# ticc.net
KiCad netlist of a schematic drawn in EAGLE
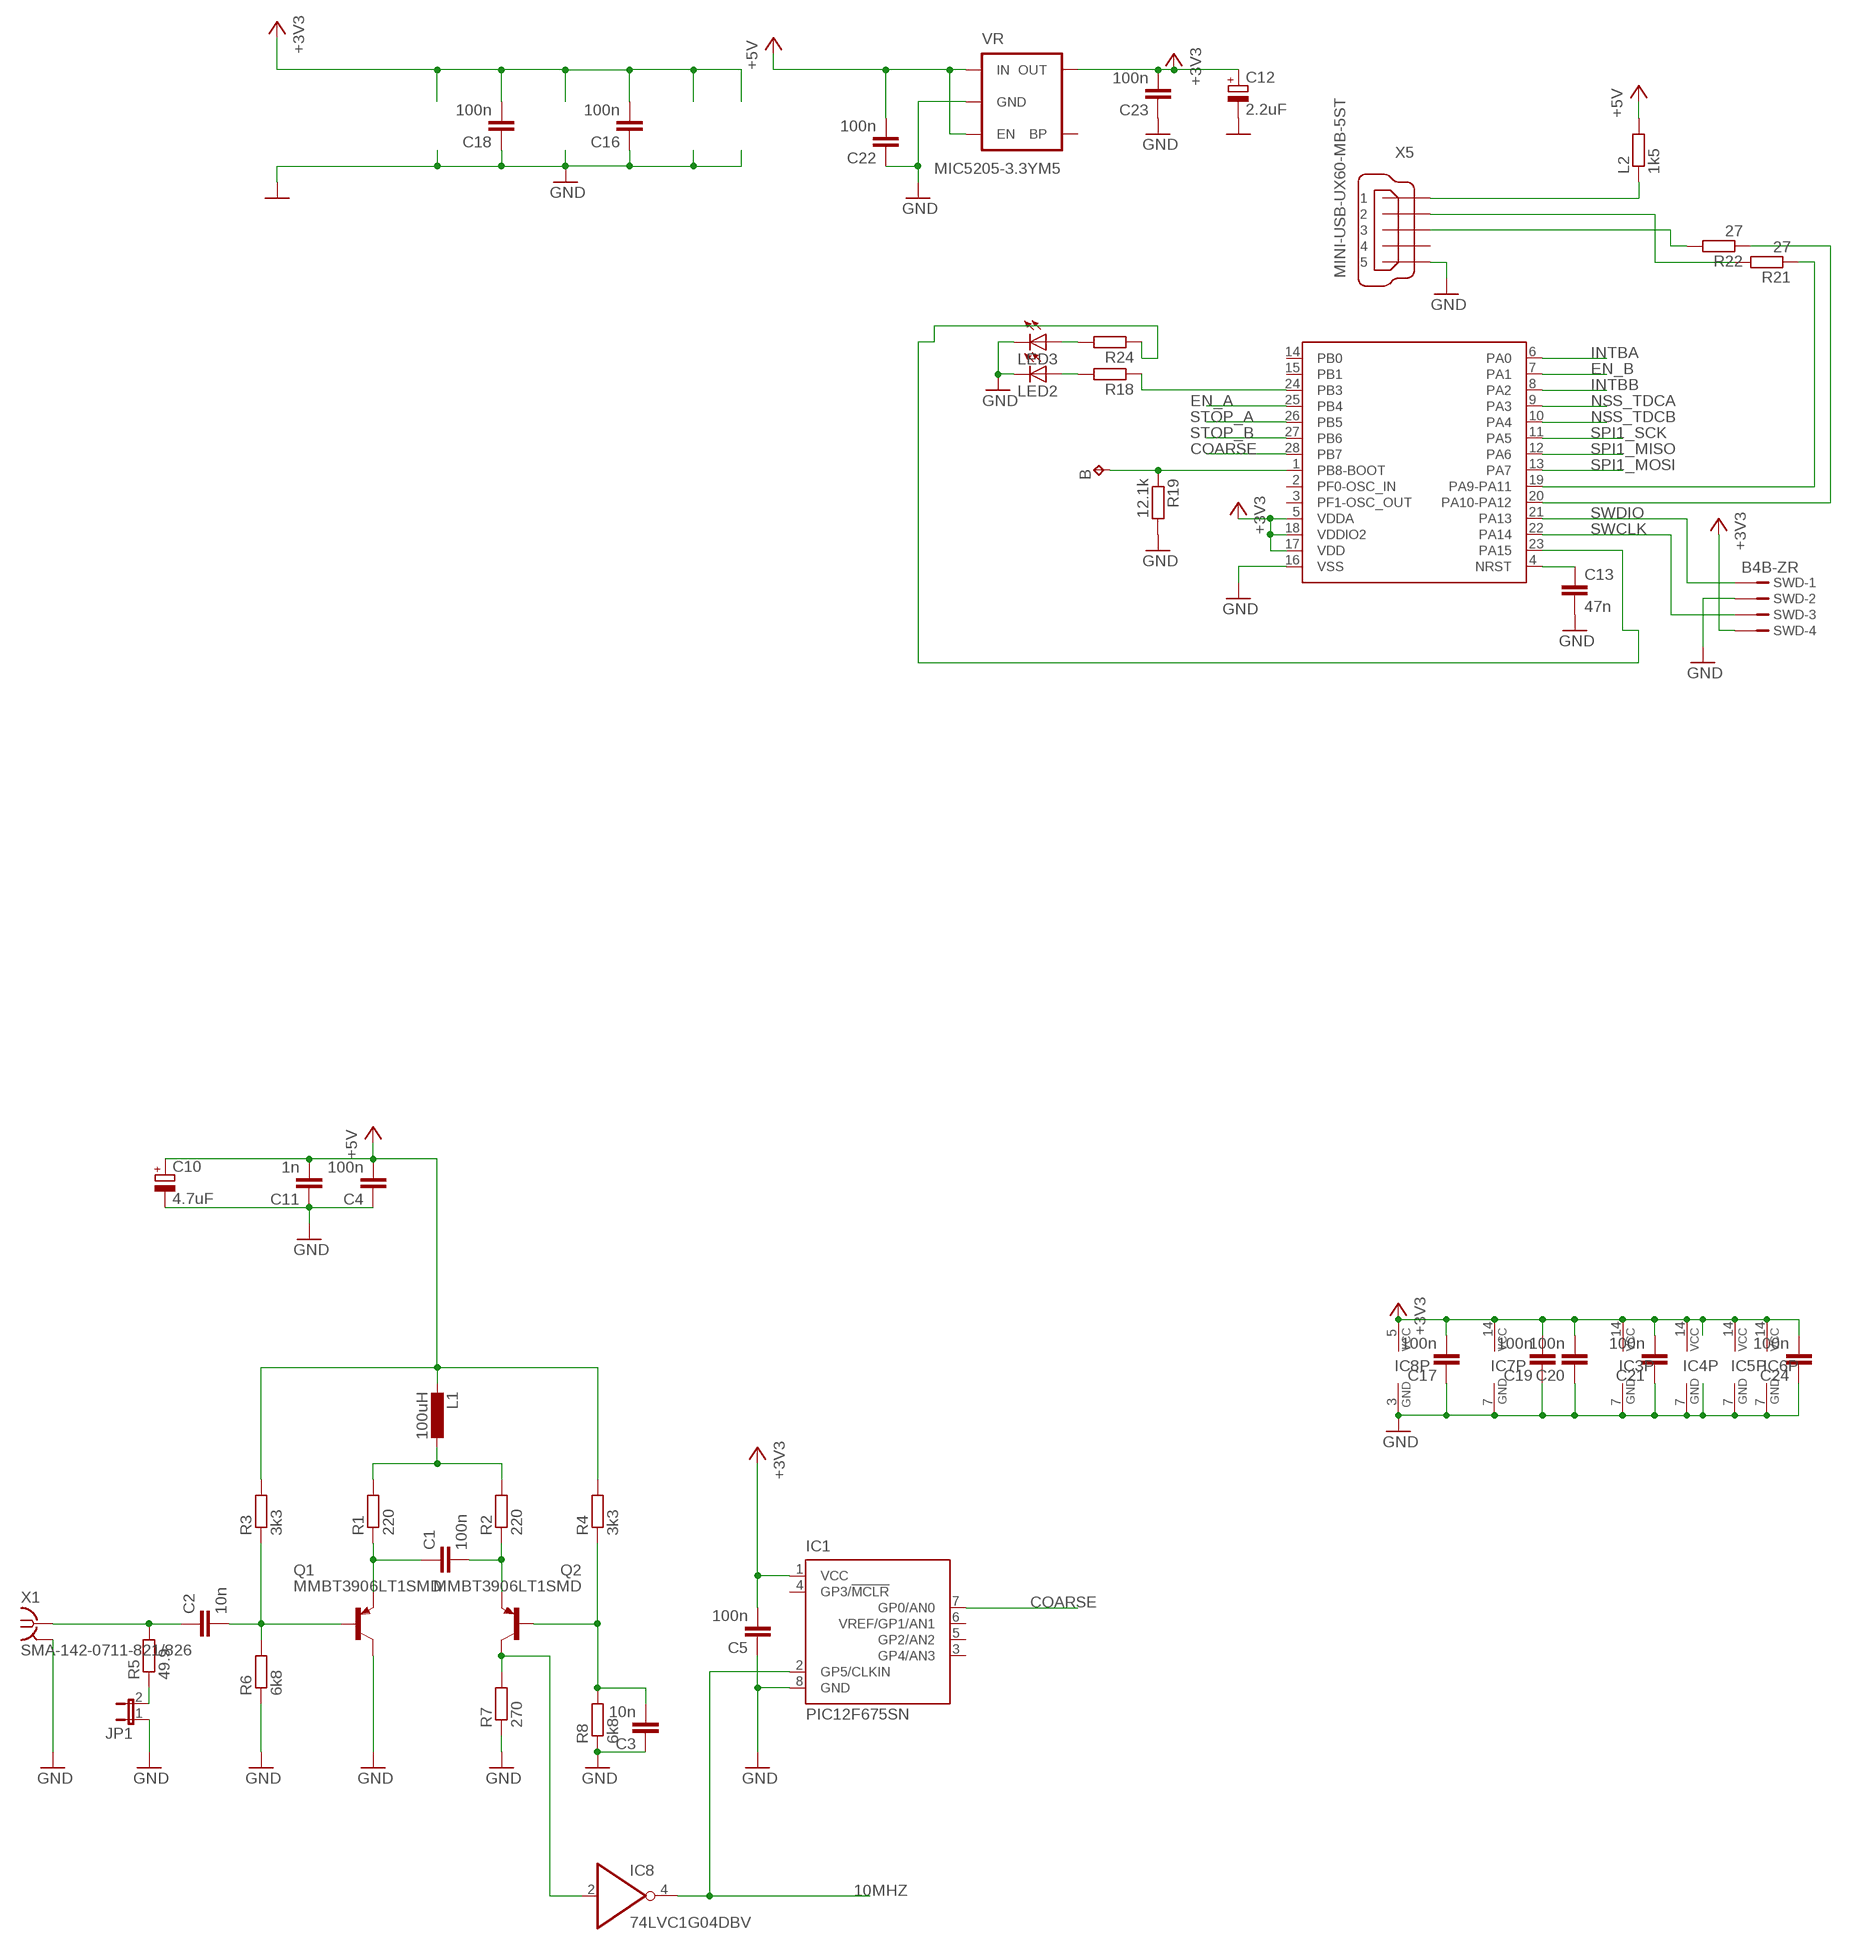
[diagram p0: schematic, sheet 1, part 1 of 2]
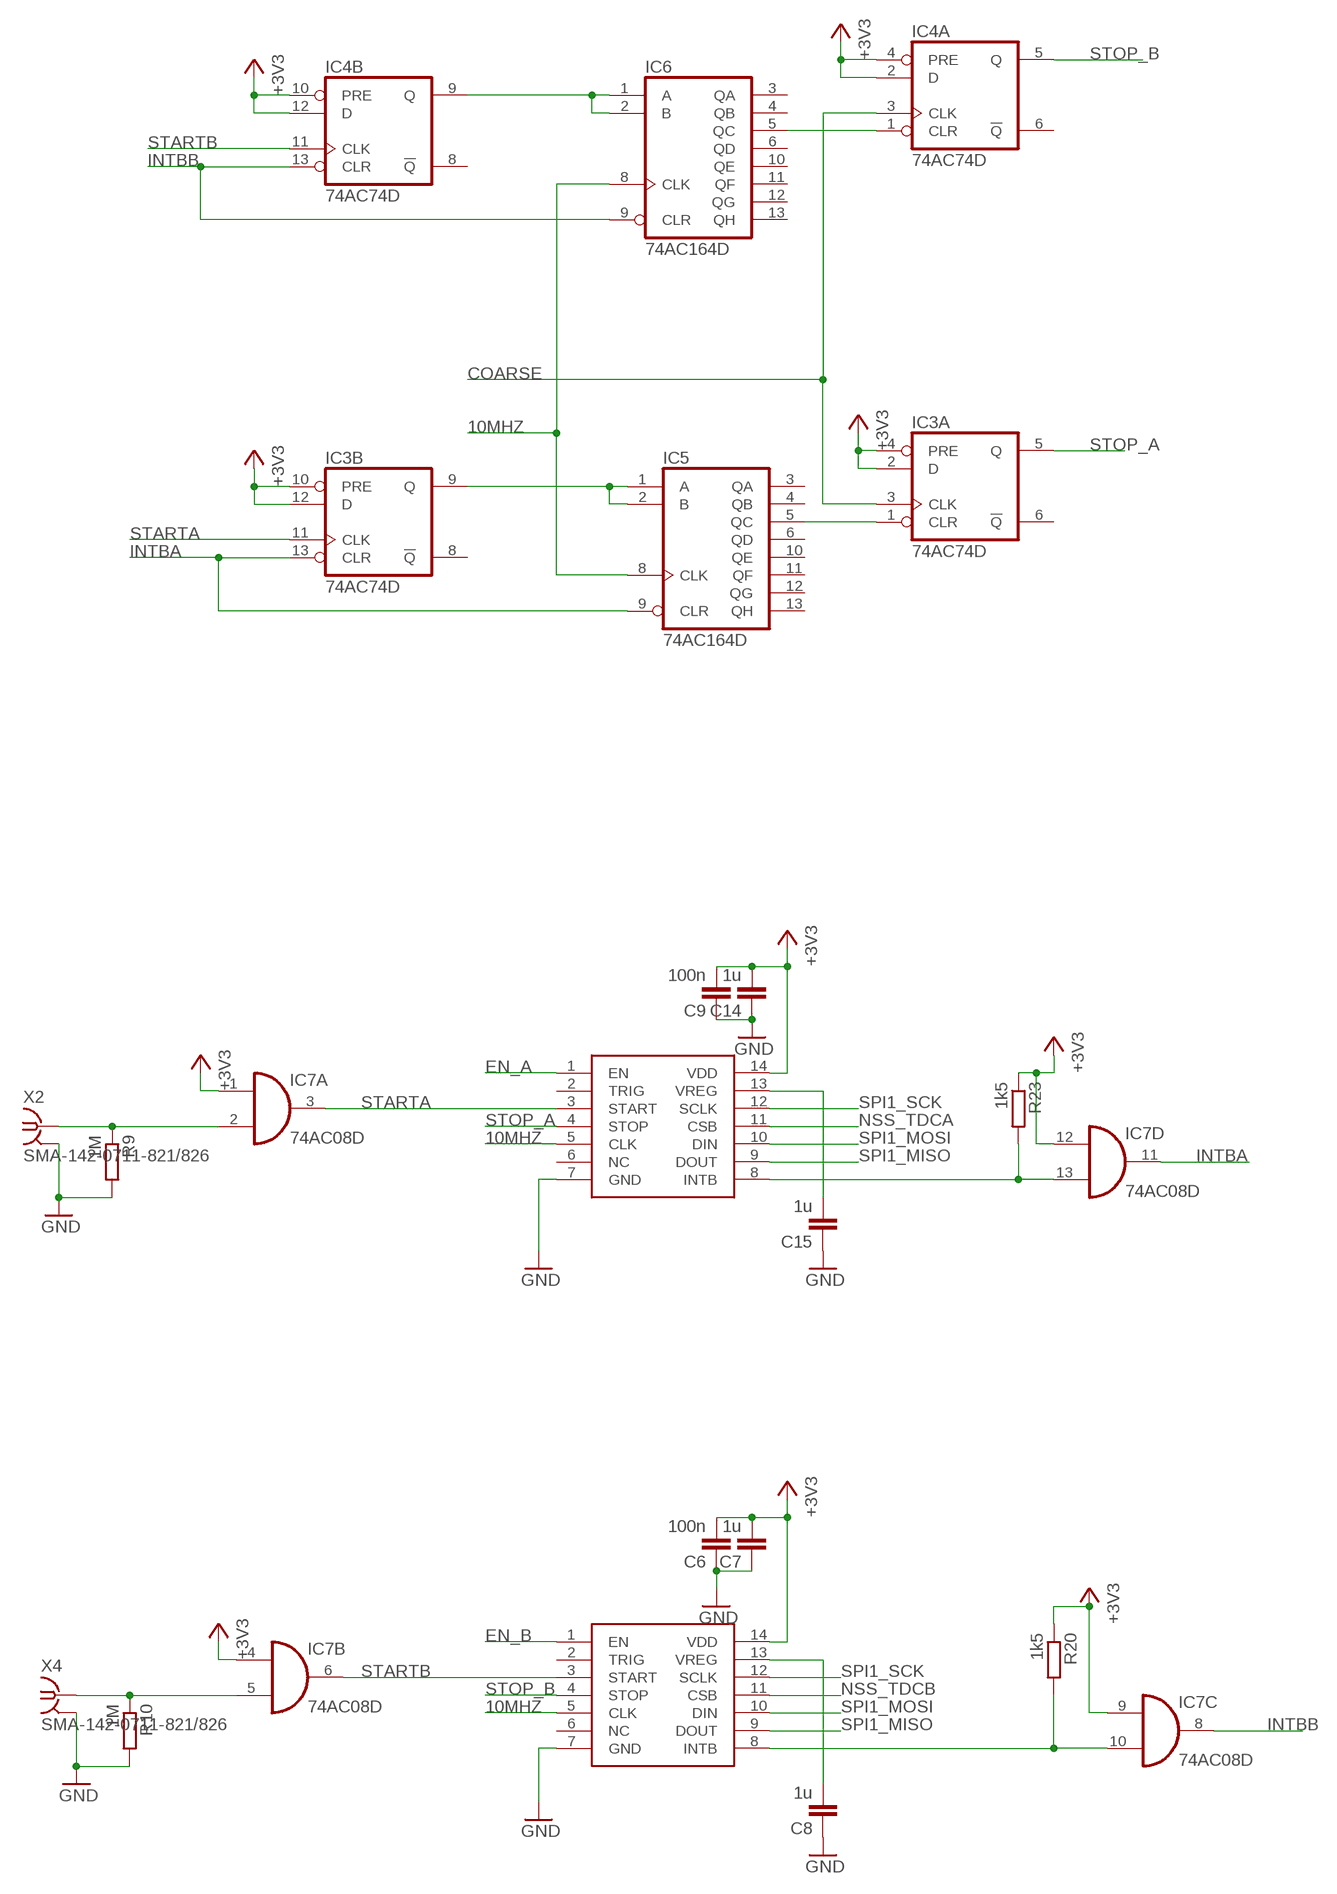
[diagram p1: schematic, sheet 1, part 2 of 2]

(export (version "E")
  (design (tool "Eeschema 10.0.6"))
  (components
    (comp (ref "B")
      (value "TPB1,27")
      (footprint "eagle-import:B1,27")
      (libsource (lib "eagle-import") (part "TPB1,27"))
    )
    (comp (ref "C1")
      (value "100n")
      (footprint "eagle-import:C0603")
      (libsource (lib "eagle-import") (part "C-EUC0603"))
    )
    (comp (ref "C2")
      (value "10n")
      (footprint "eagle-import:C0603")
      (libsource (lib "eagle-import") (part "C-EUC0603"))
    )
    (comp (ref "C3")
      (value "10n")
      (footprint "eagle-import:C0603")
      (libsource (lib "eagle-import") (part "C-EUC0603"))
    )
    (comp (ref "C4")
      (value "100n")
      (footprint "eagle-import:C0603")
      (libsource (lib "eagle-import") (part "C-EUC0603"))
    )
    (comp (ref "C5")
      (value "100n")
      (footprint "eagle-import:C0603")
      (libsource (lib "eagle-import") (part "C-EUC0603"))
    )
    (comp (ref "C6")
      (value "100n")
      (footprint "eagle-import:C0603")
      (libsource (lib "eagle-import") (part "C-EUC0603"))
    )
    (comp (ref "C7")
      (value "1u")
      (footprint "eagle-import:C0603")
      (libsource (lib "eagle-import") (part "C-EUC0603"))
    )
    (comp (ref "C8")
      (value "1u")
      (footprint "eagle-import:C0603")
      (libsource (lib "eagle-import") (part "C-EUC0603"))
    )
    (comp (ref "C9")
      (value "100n")
      (footprint "eagle-import:C0603")
      (libsource (lib "eagle-import") (part "C-EUC0603"))
    )
    (comp (ref "C10")
      (value "4.7uF")
      (footprint "eagle-import:SMC_A")
      (libsource (lib "eagle-import") (part "CPOL-EUSMCA"))
    )
    (comp (ref "C11")
      (value "1n")
      (footprint "eagle-import:C0603")
      (libsource (lib "eagle-import") (part "C-EUC0603"))
    )
    (comp (ref "C12")
      (value "2.2uF")
      (footprint "eagle-import:SMC_A")
      (libsource (lib "eagle-import") (part "CPOL-EUSMCA"))
    )
    (comp (ref "C13")
      (value "47n")
      (footprint "eagle-import:C0603")
      (libsource (lib "eagle-import") (part "C-EUC0603"))
    )
    (comp (ref "C14")
      (value "1u")
      (footprint "eagle-import:C0603")
      (libsource (lib "eagle-import") (part "C-EUC0603"))
    )
    (comp (ref "C15")
      (value "1u")
      (footprint "eagle-import:C0603")
      (libsource (lib "eagle-import") (part "C-EUC0603"))
    )
    (comp (ref "C16")
      (value "100n")
      (footprint "eagle-import:C0603")
      (libsource (lib "eagle-import") (part "C-EUC0603"))
    )
    (comp (ref "C17")
      (value "100n")
      (footprint "eagle-import:C0603")
      (libsource (lib "eagle-import") (part "C-EUC0603"))
    )
    (comp (ref "C18")
      (value "100n")
      (footprint "eagle-import:C0603")
      (libsource (lib "eagle-import") (part "C-EUC0603"))
    )
    (comp (ref "C19")
      (value "100n")
      (footprint "eagle-import:C0603")
      (libsource (lib "eagle-import") (part "C-EUC0603"))
    )
    (comp (ref "C20")
      (value "100n")
      (footprint "eagle-import:C0603")
      (libsource (lib "eagle-import") (part "C-EUC0603"))
    )
    (comp (ref "C21")
      (value "100n")
      (footprint "eagle-import:C0603")
      (libsource (lib "eagle-import") (part "C-EUC0603"))
    )
    (comp (ref "C22")
      (value "100n")
      (footprint "eagle-import:C0805K")
      (libsource (lib "eagle-import") (part "C-EUC0805K"))
    )
    (comp (ref "C23")
      (value "100n")
      (footprint "eagle-import:C0805K")
      (libsource (lib "eagle-import") (part "C-EUC0805K"))
    )
    (comp (ref "C24")
      (value "100n")
      (footprint "eagle-import:C0603")
      (libsource (lib "eagle-import") (part "C-EUC0603"))
    )
    (comp (ref "IC1")
      (value "PIC12F675SN")
      (footprint "eagle-import:SO-08")
      (fields (field (name "MF") "MICROCHIP") (field (name "MPN") "PIC12F675-E/SN"))
      (libsource (lib "eagle-import") (part "PIC12F675SN"))
    )
    (comp (ref "IC3")
      (value "74AC74D")
      (footprint "eagle-import:SO14")
      (libsource (lib "eagle-import") (part "7474DAC"))
    )
    (comp (ref "IC4")
      (value "74AC74D")
      (footprint "eagle-import:SO14")
      (libsource (lib "eagle-import") (part "7474DAC"))
    )
    (comp (ref "IC5")
      (value "74AC164D")
      (footprint "eagle-import:SO14")
      (libsource (lib "eagle-import") (part "74164DAC"))
    )
    (comp (ref "IC6")
      (value "74AC164D")
      (footprint "eagle-import:SO14")
      (libsource (lib "eagle-import") (part "74164DAC"))
    )
    (comp (ref "IC7")
      (value "74AC08D")
      (footprint "eagle-import:SO14")
      (libsource (lib "eagle-import") (part "7408DAC"))
    )
    (comp (ref "IC8")
      (value "74LVC1G04DBV")
      (footprint "eagle-import:SOT23-5")
      (libsource (lib "eagle-import") (part "741G04DBVLVC"))
    )
    (comp (ref "JP1")
      (value "JUMPER-2PTH")
      (footprint "eagle-import:1X02")
      (libsource (lib "eagle-import") (part "JUMPER-2PTH"))
    )
    (comp (ref "L1")
      (value "100uH")
      (footprint "eagle-import:L2012C")
      (libsource (lib "eagle-import") (part "L-EUL2012C"))
    )
    (comp (ref "L2")
      (value "1k5")
      (footprint "eagle-import:R0805")
      (libsource (lib "eagle-import") (part "R-EU_R0805"))
    )
    (comp (ref "LED2")
      (value "LEDCHIP-LED0805")
      (footprint "eagle-import:CHIP-LED0805")
      (libsource (lib "eagle-import") (part "LEDCHIP-LED0805"))
    )
    (comp (ref "LED3")
      (value "LEDCHIP-LED0805")
      (footprint "eagle-import:CHIP-LED0805")
      (libsource (lib "eagle-import") (part "LEDCHIP-LED0805"))
    )
    (comp (ref "Q1")
      (value "MMBT3906LT1SMD")
      (footprint "eagle-import:SOT23-BEC")
      (libsource (lib "eagle-import") (part "MMBT3906SMDLT1"))
    )
    (comp (ref "Q2")
      (value "MMBT3906LT1SMD")
      (footprint "eagle-import:SOT23-BEC")
      (libsource (lib "eagle-import") (part "MMBT3906SMDLT1"))
    )
    (comp (ref "R1")
      (value "220")
      (footprint "eagle-import:R0603")
      (libsource (lib "eagle-import") (part "R-EU_R0603"))
    )
    (comp (ref "R2")
      (value "220")
      (footprint "eagle-import:R0603")
      (libsource (lib "eagle-import") (part "R-EU_R0603"))
    )
    (comp (ref "R3")
      (value "3k3")
      (footprint "eagle-import:R0603")
      (libsource (lib "eagle-import") (part "R-EU_R0603"))
    )
    (comp (ref "R4")
      (value "3k3")
      (footprint "eagle-import:R0603")
      (libsource (lib "eagle-import") (part "R-EU_R0603"))
    )
    (comp (ref "R5")
      (value "49.9")
      (footprint "eagle-import:R0603")
      (libsource (lib "eagle-import") (part "R-EU_R0603"))
    )
    (comp (ref "R6")
      (value "6k8")
      (footprint "eagle-import:R0603")
      (libsource (lib "eagle-import") (part "R-EU_R0603"))
    )
    (comp (ref "R7")
      (value "270")
      (footprint "eagle-import:R0603")
      (libsource (lib "eagle-import") (part "R-EU_R0603"))
    )
    (comp (ref "R8")
      (value "6k8")
      (footprint "eagle-import:R0603")
      (libsource (lib "eagle-import") (part "R-EU_R0603"))
    )
    (comp (ref "R9")
      (value "1M")
      (footprint "eagle-import:R0603")
      (libsource (lib "eagle-import") (part "R-EU_R0603"))
    )
    (comp (ref "R10")
      (value "1M")
      (footprint "eagle-import:R0603")
      (libsource (lib "eagle-import") (part "R-EU_R0603"))
    )
    (comp (ref "R18")
      (value "R-EU_R0603")
      (footprint "eagle-import:R0603")
      (libsource (lib "eagle-import") (part "R-EU_R0603"))
    )
    (comp (ref "R19")
      (value "12.1k")
      (footprint "eagle-import:R0603")
      (libsource (lib "eagle-import") (part "R-EU_R0603"))
    )
    (comp (ref "R20")
      (value "1k5")
      (footprint "eagle-import:R0603")
      (libsource (lib "eagle-import") (part "R-EU_R0603"))
    )
    (comp (ref "R21")
      (value "27")
      (footprint "eagle-import:R0603")
      (libsource (lib "eagle-import") (part "R-EU_R0603"))
    )
    (comp (ref "R22")
      (value "27")
      (footprint "eagle-import:R0603")
      (libsource (lib "eagle-import") (part "R-EU_R0603"))
    )
    (comp (ref "R23")
      (value "1k5")
      (footprint "eagle-import:R0603")
      (libsource (lib "eagle-import") (part "R-EU_R0603"))
    )
    (comp (ref "R24")
      (value "R-EU_R0603")
      (footprint "eagle-import:R0603")
      (libsource (lib "eagle-import") (part "R-EU_R0603"))
    )
    (comp (ref "SWD")
      (value "B4B-ZR")
      (footprint "eagle-import:B4B-ZR")
      (fields (field (name "MF") "FARNELL") (field (name "MPN") "B4B-ZR(LF)(SN)"))
      (libsource (lib "eagle-import") (part "?4B-ZRB"))
    )
    (comp (ref "U$1")
      (value "STM32F042G")
      (footprint "eagle-import:QFN28")
      (libsource (lib "eagle-import") (part "STM32F042G"))
    )
    (comp (ref "U$2")
      (value "TDC7200")
      (footprint "eagle-import:TSSOP14")
      (libsource (lib "eagle-import") (part "TDC7200"))
    )
    (comp (ref "U$3")
      (value "TDC7200")
      (footprint "eagle-import:TSSOP14")
      (libsource (lib "eagle-import") (part "TDC7200"))
    )
    (comp (ref "VR")
      (value "MIC5205-3.3YM5")
      (footprint "eagle-import:SOT23-5")
      (libsource (lib "eagle-import") (part "V_REG_LDOSMD"))
    )
    (comp (ref "X1")
      (value "SMA-142-0711-821/826")
      (footprint "eagle-import:J502-ND-142-0711-821_826")
      (fields (field (name "MF") "JOHNSON COMPONENTS") (field (name "MPN") "142-0711-821"))
      (libsource (lib "eagle-import") (part "SMA-142-0711-821/826"))
    )
    (comp (ref "X2")
      (value "SMA-142-0711-821/826")
      (footprint "eagle-import:J502-ND-142-0711-821_826")
      (fields (field (name "MF") "JOHNSON COMPONENTS") (field (name "MPN") "142-0711-821"))
      (libsource (lib "eagle-import") (part "SMA-142-0711-821/826"))
    )
    (comp (ref "X4")
      (value "SMA-142-0711-821/826")
      (footprint "eagle-import:J502-ND-142-0711-821_826")
      (fields (field (name "MF") "JOHNSON COMPONENTS") (field (name "MPN") "142-0711-821"))
      (libsource (lib "eagle-import") (part "SMA-142-0711-821/826"))
    )
    (comp (ref "X5")
      (value "MINI-USB-UX60-MB-5ST")
      (footprint "eagle-import:UX60-MB-5ST")
      (libsource (lib "eagle-import") (part "MINI-USB-UX60-MB-5ST"))
    )
  )
  (nets
    (net (code "1") (name "+3V3") (class "Default")
      (node (ref "C12") (pin "+") (pinfunction "+_+") (pintype "passive"))
      (node (ref "C14") (pin "2") (pinfunction "2_2") (pintype "passive"))
      (node (ref "C16") (pin "2") (pinfunction "2_2") (pintype "passive"))
      (node (ref "C17") (pin "2") (pinfunction "2_2") (pintype "passive"))
      (node (ref "C18") (pin "2") (pinfunction "2_2") (pintype "passive"))
      (node (ref "C19") (pin "2") (pinfunction "2_2") (pintype "passive"))
      (node (ref "C20") (pin "2") (pinfunction "2_2") (pintype "passive"))
      (node (ref "C21") (pin "2") (pinfunction "2_2") (pintype "passive"))
      (node (ref "C23") (pin "2") (pinfunction "2_2") (pintype "passive"))
      (node (ref "C24") (pin "2") (pinfunction "2_2") (pintype "passive"))
      (node (ref "C5") (pin "2") (pinfunction "2_2") (pintype "passive"))
      (node (ref "C6") (pin "2") (pinfunction "2_2") (pintype "passive"))
      (node (ref "C7") (pin "2") (pinfunction "2_2") (pintype "passive"))
      (node (ref "C9") (pin "2") (pinfunction "2_2") (pintype "passive"))
      (node (ref "IC1") (pin "1") (pinfunction "VCC_1") (pintype "power_in"))
      (node (ref "IC3") (pin "10") (pinfunction "PRE_10") (pintype "input"))
      (node (ref "IC3") (pin "12") (pinfunction "D_12") (pintype "input"))
      (node (ref "IC3") (pin "14") (pinfunction "VCC_14") (pintype "power_in"))
      (node (ref "IC3") (pin "2") (pinfunction "D_2") (pintype "input"))
      (node (ref "IC3") (pin "4") (pinfunction "PRE_4") (pintype "input"))
      (node (ref "IC4") (pin "10") (pinfunction "PRE_10") (pintype "input"))
      (node (ref "IC4") (pin "12") (pinfunction "D_12") (pintype "input"))
      (node (ref "IC4") (pin "14") (pinfunction "VCC_14") (pintype "power_in"))
      (node (ref "IC4") (pin "2") (pinfunction "D_2") (pintype "input"))
      (node (ref "IC4") (pin "4") (pinfunction "PRE_4") (pintype "input"))
      (node (ref "IC5") (pin "14") (pinfunction "VCC_14") (pintype "power_in"))
      (node (ref "IC6") (pin "14") (pinfunction "VCC_14") (pintype "power_in"))
      (node (ref "IC7") (pin "1") (pinfunction "I0_1") (pintype "input"))
      (node (ref "IC7") (pin "12") (pinfunction "I0_12") (pintype "input"))
      (node (ref "IC7") (pin "14") (pinfunction "VCC_14") (pintype "power_in"))
      (node (ref "IC7") (pin "4") (pinfunction "I0_4") (pintype "input"))
      (node (ref "IC7") (pin "9") (pinfunction "I0_9") (pintype "input"))
      (node (ref "IC8") (pin "5") (pinfunction "VCC_5") (pintype "power_in"))
      (node (ref "R20") (pin "1") (pinfunction "1_1") (pintype "passive"))
      (node (ref "R23") (pin "1") (pinfunction "1_1") (pintype "passive"))
      (node (ref "SWD") (pin "4") (pinfunction "1_4") (pintype "passive"))
      (node (ref "U$1") (pin "17") (pinfunction "VDD_17") (pintype "bidirectional"))
      (node (ref "U$1") (pin "18") (pinfunction "VDDIO2_18") (pintype "bidirectional"))
      (node (ref "U$1") (pin "5") (pinfunction "VDDA_5") (pintype "bidirectional"))
      (node (ref "U$2") (pin "14") (pinfunction "VDD_14") (pintype "bidirectional"))
      (node (ref "U$3") (pin "14") (pinfunction "VDD_14") (pintype "bidirectional"))
      (node (ref "VR") (pin "5") (pinfunction "OUT_5") (pintype "passive"))
    )
    (net (code "2") (name "+5V") (class "Default")
      (node (ref "C10") (pin "+") (pinfunction "+_+") (pintype "passive"))
      (node (ref "C11") (pin "2") (pinfunction "2_2") (pintype "passive"))
      (node (ref "C22") (pin "2") (pinfunction "2_2") (pintype "passive"))
      (node (ref "C4") (pin "2") (pinfunction "2_2") (pintype "passive"))
      (node (ref "L1") (pin "2") (pinfunction "2_2") (pintype "passive"))
      (node (ref "L2") (pin "2") (pinfunction "2_2") (pintype "passive"))
      (node (ref "R3") (pin "2") (pinfunction "2_2") (pintype "passive"))
      (node (ref "R4") (pin "2") (pinfunction "2_2") (pintype "passive"))
      (node (ref "VR") (pin "1") (pinfunction "IN_1") (pintype "input"))
      (node (ref "VR") (pin "3") (pinfunction "EN_3") (pintype "input"))
    )
    (net (code "3") (name "/10MHZ") (class "Default")
      (node (ref "IC1") (pin "2") (pinfunction "GP5/CLKIN_2") (pintype "bidirectional"))
      (node (ref "IC5") (pin "8") (pinfunction "CLK_8") (pintype "input"))
      (node (ref "IC6") (pin "8") (pinfunction "CLK_8") (pintype "input"))
      (node (ref "IC8") (pin "4") (pinfunction "O_4") (pintype "output"))
      (node (ref "U$2") (pin "5") (pinfunction "CLK_5") (pintype "bidirectional"))
      (node (ref "U$3") (pin "5") (pinfunction "CLK_5") (pintype "bidirectional"))
    )
    (net (code "4") (name "/COARSE") (class "Default")
      (node (ref "IC1") (pin "7") (pinfunction "GP0/AN0_7") (pintype "bidirectional"))
      (node (ref "IC3") (pin "3") (pinfunction "CLK_3") (pintype "input"))
      (node (ref "IC4") (pin "3") (pinfunction "CLK_3") (pintype "input"))
      (node (ref "U$1") (pin "28") (pinfunction "PB7_28") (pintype "bidirectional"))
    )
    (net (code "5") (name "/EN_A") (class "Default")
      (node (ref "U$1") (pin "25") (pinfunction "PB4_25") (pintype "bidirectional"))
      (node (ref "U$2") (pin "1") (pinfunction "EN_1") (pintype "bidirectional"))
    )
    (net (code "6") (name "/EN_B") (class "Default")
      (node (ref "U$1") (pin "7") (pinfunction "PA1_7") (pintype "bidirectional"))
      (node (ref "U$3") (pin "1") (pinfunction "EN_1") (pintype "bidirectional"))
    )
    (net (code "7") (name "/INTBA") (class "Default")
      (node (ref "IC3") (pin "13") (pinfunction "CLR_13") (pintype "input"))
      (node (ref "IC5") (pin "9") (pinfunction "CLR_9") (pintype "input"))
      (node (ref "IC7") (pin "11") (pinfunction "O_11") (pintype "output"))
      (node (ref "U$1") (pin "6") (pinfunction "PA0_6") (pintype "bidirectional"))
    )
    (net (code "8") (name "/INTBB") (class "Default")
      (node (ref "IC4") (pin "13") (pinfunction "CLR_13") (pintype "input"))
      (node (ref "IC6") (pin "9") (pinfunction "CLR_9") (pintype "input"))
      (node (ref "IC7") (pin "8") (pinfunction "O_8") (pintype "output"))
      (node (ref "U$1") (pin "8") (pinfunction "PA2_8") (pintype "bidirectional"))
    )
    (net (code "9") (name "/NSS_TDCA") (class "Default")
      (node (ref "U$1") (pin "9") (pinfunction "PA3_9") (pintype "bidirectional"))
      (node (ref "U$2") (pin "11") (pinfunction "CSB_11") (pintype "bidirectional"))
    )
    (net (code "10") (name "/NSS_TDCB") (class "Default")
      (node (ref "U$1") (pin "10") (pinfunction "PA4_10") (pintype "bidirectional"))
      (node (ref "U$3") (pin "11") (pinfunction "CSB_11") (pintype "bidirectional"))
    )
    (net (code "11") (name "/SPI1_MISO") (class "Default")
      (node (ref "U$1") (pin "12") (pinfunction "PA6_12") (pintype "bidirectional"))
      (node (ref "U$2") (pin "9") (pinfunction "DOUT_9") (pintype "bidirectional"))
      (node (ref "U$3") (pin "9") (pinfunction "DOUT_9") (pintype "bidirectional"))
    )
    (net (code "12") (name "/SPI1_MOSI") (class "Default")
      (node (ref "U$1") (pin "13") (pinfunction "PA7_13") (pintype "bidirectional"))
      (node (ref "U$2") (pin "10") (pinfunction "DIN_10") (pintype "bidirectional"))
      (node (ref "U$3") (pin "10") (pinfunction "DIN_10") (pintype "bidirectional"))
    )
    (net (code "13") (name "/SPI1_SCK") (class "Default")
      (node (ref "U$1") (pin "11") (pinfunction "PA5_11") (pintype "bidirectional"))
      (node (ref "U$2") (pin "12") (pinfunction "SCLK_12") (pintype "bidirectional"))
      (node (ref "U$3") (pin "12") (pinfunction "SCLK_12") (pintype "bidirectional"))
    )
    (net (code "14") (name "/STARTA") (class "Default")
      (node (ref "IC3") (pin "11") (pinfunction "CLK_11") (pintype "input"))
      (node (ref "IC7") (pin "3") (pinfunction "O_3") (pintype "output"))
      (node (ref "U$2") (pin "3") (pinfunction "START_3") (pintype "bidirectional"))
    )
    (net (code "15") (name "/STARTB") (class "Default")
      (node (ref "IC4") (pin "11") (pinfunction "CLK_11") (pintype "input"))
      (node (ref "IC7") (pin "6") (pinfunction "O_6") (pintype "output"))
      (node (ref "U$3") (pin "3") (pinfunction "START_3") (pintype "bidirectional"))
    )
    (net (code "16") (name "/STOP_A") (class "Default")
      (node (ref "IC3") (pin "5") (pinfunction "Q_5") (pintype "output"))
      (node (ref "U$1") (pin "26") (pinfunction "PB5_26") (pintype "bidirectional"))
      (node (ref "U$2") (pin "4") (pinfunction "STOP_4") (pintype "bidirectional"))
    )
    (net (code "17") (name "/STOP_B") (class "Default")
      (node (ref "IC4") (pin "5") (pinfunction "Q_5") (pintype "output"))
      (node (ref "U$1") (pin "27") (pinfunction "PB6_27") (pintype "bidirectional"))
      (node (ref "U$3") (pin "4") (pinfunction "STOP_4") (pintype "bidirectional"))
    )
    (net (code "18") (name "/SWCLK") (class "Default")
      (node (ref "SWD") (pin "3") (pinfunction "1_3") (pintype "passive"))
      (node (ref "U$1") (pin "22") (pinfunction "PA14_22") (pintype "bidirectional"))
    )
    (net (code "19") (name "/SWDIO") (class "Default")
      (node (ref "SWD") (pin "1") (pinfunction "1_1") (pintype "passive"))
      (node (ref "U$1") (pin "21") (pinfunction "PA13_21") (pintype "bidirectional"))
    )
    (net (code "20") (name "GND") (class "Default")
      (node (ref "C10") (pin "-") (pinfunction "-_-") (pintype "passive"))
      (node (ref "C11") (pin "1") (pinfunction "1_1") (pintype "passive"))
      (node (ref "C12") (pin "-") (pinfunction "-_-") (pintype "passive"))
      (node (ref "C13") (pin "2") (pinfunction "2_2") (pintype "passive"))
      (node (ref "C14") (pin "1") (pinfunction "1_1") (pintype "passive"))
      (node (ref "C15") (pin "1") (pinfunction "1_1") (pintype "passive"))
      (node (ref "C16") (pin "1") (pinfunction "1_1") (pintype "passive"))
      (node (ref "C17") (pin "1") (pinfunction "1_1") (pintype "passive"))
      (node (ref "C18") (pin "1") (pinfunction "1_1") (pintype "passive"))
      (node (ref "C19") (pin "1") (pinfunction "1_1") (pintype "passive"))
      (node (ref "C20") (pin "1") (pinfunction "1_1") (pintype "passive"))
      (node (ref "C21") (pin "1") (pinfunction "1_1") (pintype "passive"))
      (node (ref "C22") (pin "1") (pinfunction "1_1") (pintype "passive"))
      (node (ref "C23") (pin "1") (pinfunction "1_1") (pintype "passive"))
      (node (ref "C24") (pin "1") (pinfunction "1_1") (pintype "passive"))
      (node (ref "C3") (pin "1") (pinfunction "1_1") (pintype "passive"))
      (node (ref "C4") (pin "1") (pinfunction "1_1") (pintype "passive"))
      (node (ref "C5") (pin "1") (pinfunction "1_1") (pintype "passive"))
      (node (ref "C6") (pin "1") (pinfunction "1_1") (pintype "passive"))
      (node (ref "C7") (pin "1") (pinfunction "1_1") (pintype "passive"))
      (node (ref "C8") (pin "1") (pinfunction "1_1") (pintype "passive"))
      (node (ref "C9") (pin "1") (pinfunction "1_1") (pintype "passive"))
      (node (ref "IC1") (pin "8") (pinfunction "GND_8") (pintype "power_in"))
      (node (ref "IC3") (pin "7") (pinfunction "GND_7") (pintype "power_in"))
      (node (ref "IC4") (pin "7") (pinfunction "GND_7") (pintype "power_in"))
      (node (ref "IC5") (pin "7") (pinfunction "GND_7") (pintype "power_in"))
      (node (ref "IC6") (pin "7") (pinfunction "GND_7") (pintype "power_in"))
      (node (ref "IC7") (pin "7") (pinfunction "GND_7") (pintype "power_in"))
      (node (ref "IC8") (pin "3") (pinfunction "GND_3") (pintype "power_in"))
      (node (ref "JP1") (pin "1") (pinfunction "1_1") (pintype "passive"))
      (node (ref "LED2") (pin "C") (pinfunction "C_C") (pintype "passive"))
      (node (ref "LED3") (pin "C") (pinfunction "C_C") (pintype "passive"))
      (node (ref "Q1") (pin "C") (pinfunction "C_C") (pintype "passive"))
      (node (ref "R10") (pin "2") (pinfunction "2_2") (pintype "passive"))
      (node (ref "R19") (pin "2") (pinfunction "2_2") (pintype "passive"))
      (node (ref "R6") (pin "1") (pinfunction "1_1") (pintype "passive"))
      (node (ref "R7") (pin "1") (pinfunction "1_1") (pintype "passive"))
      (node (ref "R8") (pin "1") (pinfunction "1_1") (pintype "passive"))
      (node (ref "R9") (pin "2") (pinfunction "2_2") (pintype "passive"))
      (node (ref "SWD") (pin "2") (pinfunction "1_2") (pintype "passive"))
      (node (ref "U$1") (pin "16") (pinfunction "VSS_16") (pintype "bidirectional"))
      (node (ref "U$2") (pin "7") (pinfunction "GND_7") (pintype "bidirectional"))
      (node (ref "U$3") (pin "7") (pinfunction "GND_7") (pintype "bidirectional"))
      (node (ref "VR") (pin "2") (pinfunction "GND_2") (pintype "input"))
      (node (ref "X1") (pin "G@1") (pinfunction "GND_G@1") (pintype "power_in"))
      (node (ref "X2") (pin "G@1") (pinfunction "GND_G@1") (pintype "power_in"))
      (node (ref "X4") (pin "G@1") (pinfunction "GND_G@1") (pintype "power_in"))
      (node (ref "X5") (pin "5") (pinfunction "5_5") (pintype "input"))
    )
    (net (code "21") (name "Net-(B-TP)") (class "Default")
      (node (ref "B") (pin "PP") (pinfunction "TP_PP") (pintype "input"))
      (node (ref "R19") (pin "1") (pinfunction "1_1") (pintype "passive"))
      (node (ref "U$1") (pin "1") (pinfunction "PB8-BOOT_1") (pintype "bidirectional"))
    )
    (net (code "22") (name "Net-(C1-Pad1)") (class "Default")
      (node (ref "C1") (pin "1") (pinfunction "1_1") (pintype "passive"))
      (node (ref "Q1") (pin "E") (pinfunction "E_E") (pintype "passive"))
      (node (ref "R1") (pin "1") (pinfunction "1_1") (pintype "passive"))
    )
    (net (code "23") (name "Net-(C1-Pad2)") (class "Default")
      (node (ref "C1") (pin "2") (pinfunction "2_2") (pintype "passive"))
      (node (ref "Q2") (pin "E") (pinfunction "E_E") (pintype "passive"))
      (node (ref "R2") (pin "1") (pinfunction "1_1") (pintype "passive"))
    )
    (net (code "24") (name "Net-(C2-Pad1)") (class "Default")
      (node (ref "C2") (pin "1") (pinfunction "1_1") (pintype "passive"))
      (node (ref "R5") (pin "2") (pinfunction "2_2") (pintype "passive"))
      (node (ref "X1") (pin "1") (pinfunction "1_1") (pintype "passive"))
    )
    (net (code "25") (name "Net-(C2-Pad2)") (class "Default")
      (node (ref "C2") (pin "2") (pinfunction "2_2") (pintype "passive"))
      (node (ref "Q1") (pin "B") (pinfunction "B_B") (pintype "passive"))
      (node (ref "R3") (pin "1") (pinfunction "1_1") (pintype "passive"))
      (node (ref "R6") (pin "2") (pinfunction "2_2") (pintype "passive"))
    )
    (net (code "26") (name "Net-(C3-Pad2)") (class "Default")
      (node (ref "C3") (pin "2") (pinfunction "2_2") (pintype "passive"))
      (node (ref "Q2") (pin "B") (pinfunction "B_B") (pintype "passive"))
      (node (ref "R4") (pin "1") (pinfunction "1_1") (pintype "passive"))
      (node (ref "R8") (pin "2") (pinfunction "2_2") (pintype "passive"))
    )
    (net (code "27") (name "Net-(IC3A-CLR)") (class "Default")
      (node (ref "IC3") (pin "1") (pinfunction "CLR_1") (pintype "input"))
      (node (ref "IC5") (pin "5") (pinfunction "QC_5") (pintype "output"))
    )
    (net (code "28") (name "Net-(IC3B-Q)") (class "Default")
      (node (ref "IC3") (pin "9") (pinfunction "Q_9") (pintype "output"))
      (node (ref "IC5") (pin "1") (pinfunction "A_1") (pintype "input"))
      (node (ref "IC5") (pin "2") (pinfunction "B_2") (pintype "input"))
    )
    (net (code "29") (name "Net-(IC4A-CLR)") (class "Default")
      (node (ref "IC4") (pin "1") (pinfunction "CLR_1") (pintype "input"))
      (node (ref "IC6") (pin "5") (pinfunction "QC_5") (pintype "output"))
    )
    (net (code "30") (name "Net-(IC4B-Q)") (class "Default")
      (node (ref "IC4") (pin "9") (pinfunction "Q_9") (pintype "output"))
      (node (ref "IC6") (pin "1") (pinfunction "A_1") (pintype "input"))
      (node (ref "IC6") (pin "2") (pinfunction "B_2") (pintype "input"))
    )
    (net (code "31") (name "Net-(IC7A-I1)") (class "Default")
      (node (ref "IC7") (pin "2") (pinfunction "I1_2") (pintype "input"))
      (node (ref "R9") (pin "1") (pinfunction "1_1") (pintype "passive"))
      (node (ref "X2") (pin "1") (pinfunction "1_1") (pintype "passive"))
    )
    (net (code "32") (name "Net-(IC7B-I1)") (class "Default")
      (node (ref "IC7") (pin "5") (pinfunction "I1_5") (pintype "input"))
      (node (ref "R10") (pin "1") (pinfunction "1_1") (pintype "passive"))
      (node (ref "X4") (pin "1") (pinfunction "1_1") (pintype "passive"))
    )
    (net (code "33") (name "Net-(IC7C-I1)") (class "Default")
      (node (ref "IC7") (pin "10") (pinfunction "I1_10") (pintype "input"))
      (node (ref "R20") (pin "2") (pinfunction "2_2") (pintype "passive"))
      (node (ref "U$3") (pin "8") (pinfunction "INTB_8") (pintype "bidirectional"))
    )
    (net (code "34") (name "Net-(IC7D-I1)") (class "Default")
      (node (ref "IC7") (pin "13") (pinfunction "I1_13") (pintype "input"))
      (node (ref "R23") (pin "2") (pinfunction "2_2") (pintype "passive"))
      (node (ref "U$2") (pin "8") (pinfunction "INTB_8") (pintype "bidirectional"))
    )
    (net (code "35") (name "Net-(IC8A-I)") (class "Default")
      (node (ref "IC8") (pin "2") (pinfunction "I_2") (pintype "input"))
      (node (ref "Q2") (pin "C") (pinfunction "C_C") (pintype "passive"))
      (node (ref "R7") (pin "2") (pinfunction "2_2") (pintype "passive"))
    )
    (net (code "36") (name "Net-(JP1-Pad2)") (class "Default")
      (node (ref "JP1") (pin "2") (pinfunction "2_2") (pintype "passive"))
      (node (ref "R5") (pin "1") (pinfunction "1_1") (pintype "passive"))
    )
    (net (code "37") (name "Net-(L1-Pad1)") (class "Default")
      (node (ref "L1") (pin "1") (pinfunction "1_1") (pintype "passive"))
      (node (ref "R1") (pin "2") (pinfunction "2_2") (pintype "passive"))
      (node (ref "R2") (pin "2") (pinfunction "2_2") (pintype "passive"))
    )
    (net (code "38") (name "Net-(L2-Pad1)") (class "Default")
      (node (ref "L2") (pin "1") (pinfunction "1_1") (pintype "passive"))
      (node (ref "X5") (pin "1") (pinfunction "1_1") (pintype "input"))
    )
    (net (code "39") (name "Net-(LED2-PadA)") (class "Default")
      (node (ref "LED2") (pin "A") (pinfunction "A_A") (pintype "passive"))
      (node (ref "R18") (pin "2") (pinfunction "2_2") (pintype "passive"))
    )
    (net (code "40") (name "Net-(LED3-PadA)") (class "Default")
      (node (ref "LED3") (pin "A") (pinfunction "A_A") (pintype "passive"))
      (node (ref "R24") (pin "2") (pinfunction "2_2") (pintype "passive"))
    )
    (net (code "41") (name "Net-(R21-Pad2)") (class "Default")
      (node (ref "R21") (pin "2") (pinfunction "2_2") (pintype "passive"))
      (node (ref "X5") (pin "2") (pinfunction "2_2") (pintype "input"))
    )
    (net (code "42") (name "Net-(R22-Pad2)") (class "Default")
      (node (ref "R22") (pin "2") (pinfunction "2_2") (pintype "passive"))
      (node (ref "X5") (pin "3") (pinfunction "3_3") (pintype "input"))
    )
    (net (code "43") (name "Net-(U$1-NRST)") (class "Default")
      (node (ref "C13") (pin "1") (pinfunction "1_1") (pintype "passive"))
      (node (ref "U$1") (pin "4") (pinfunction "NRST_4") (pintype "bidirectional"))
    )
    (net (code "44") (name "Net-(U$1-PA9-PA11)") (class "Default")
      (node (ref "R21") (pin "1") (pinfunction "1_1") (pintype "passive"))
      (node (ref "U$1") (pin "19") (pinfunction "PA9-PA11_19") (pintype "bidirectional"))
    )
    (net (code "45") (name "Net-(U$1-PA10-PA12)") (class "Default")
      (node (ref "R22") (pin "1") (pinfunction "1_1") (pintype "passive"))
      (node (ref "U$1") (pin "20") (pinfunction "PA10-PA12_20") (pintype "bidirectional"))
    )
    (net (code "46") (name "Net-(U$1-PA15)") (class "Default")
      (node (ref "R24") (pin "1") (pinfunction "1_1") (pintype "passive"))
      (node (ref "U$1") (pin "23") (pinfunction "PA15_23") (pintype "bidirectional"))
    )
    (net (code "47") (name "Net-(U$1-PB3)") (class "Default")
      (node (ref "R18") (pin "1") (pinfunction "1_1") (pintype "passive"))
      (node (ref "U$1") (pin "24") (pinfunction "PB3_24") (pintype "bidirectional"))
    )
    (net (code "48") (name "Net-(U$2-VREG)") (class "Default")
      (node (ref "C15") (pin "2") (pinfunction "2_2") (pintype "passive"))
      (node (ref "U$2") (pin "13") (pinfunction "VREG_13") (pintype "bidirectional"))
    )
    (net (code "49") (name "Net-(U$3-VREG)") (class "Default")
      (node (ref "C8") (pin "2") (pinfunction "2_2") (pintype "passive"))
      (node (ref "U$3") (pin "13") (pinfunction "VREG_13") (pintype "bidirectional"))
    )
    (net (code "50") (name "unconnected-(IC1-GP2{slash}AN2-Pad5)") (class "Default")
      (node (ref "IC1") (pin "5") (pinfunction "GP2/AN2_5") (pintype "bidirectional"))
    )
    (net (code "51") (name "unconnected-(IC1-GP3{slash}~{MCLR}-Pad4)") (class "Default")
      (node (ref "IC1") (pin "4") (pinfunction "GP3/~{MCLR}_4") (pintype "input"))
    )
    (net (code "52") (name "unconnected-(IC1-GP4{slash}AN3-Pad3)") (class "Default")
      (node (ref "IC1") (pin "3") (pinfunction "GP4/AN3_3") (pintype "bidirectional"))
    )
    (net (code "53") (name "unconnected-(IC1-VREF{slash}GP1{slash}AN1-Pad6)") (class "Default")
      (node (ref "IC1") (pin "6") (pinfunction "VREF/GP1/AN1_6") (pintype "bidirectional"))
    )
    (net (code "54") (name "unconnected-(IC3A-~{Q}-Pad6)") (class "Default")
      (node (ref "IC3") (pin "6") (pinfunction "~{Q}_6") (pintype "output"))
    )
    (net (code "55") (name "unconnected-(IC3B-~{Q}-Pad8)") (class "Default")
      (node (ref "IC3") (pin "8") (pinfunction "~{Q}_8") (pintype "output"))
    )
    (net (code "56") (name "unconnected-(IC4A-~{Q}-Pad6)") (class "Default")
      (node (ref "IC4") (pin "6") (pinfunction "~{Q}_6") (pintype "output"))
    )
    (net (code "57") (name "unconnected-(IC4B-~{Q}-Pad8)") (class "Default")
      (node (ref "IC4") (pin "8") (pinfunction "~{Q}_8") (pintype "output"))
    )
    (net (code "58") (name "unconnected-(IC5A-QA-Pad3)") (class "Default")
      (node (ref "IC5") (pin "3") (pinfunction "QA_3") (pintype "output"))
    )
    (net (code "59") (name "unconnected-(IC5A-QB-Pad4)") (class "Default")
      (node (ref "IC5") (pin "4") (pinfunction "QB_4") (pintype "output"))
    )
    (net (code "60") (name "unconnected-(IC5A-QD-Pad6)") (class "Default")
      (node (ref "IC5") (pin "6") (pinfunction "QD_6") (pintype "output"))
    )
    (net (code "61") (name "unconnected-(IC5A-QE-Pad10)") (class "Default")
      (node (ref "IC5") (pin "10") (pinfunction "QE_10") (pintype "output"))
    )
    (net (code "62") (name "unconnected-(IC5A-QF-Pad11)") (class "Default")
      (node (ref "IC5") (pin "11") (pinfunction "QF_11") (pintype "output"))
    )
    (net (code "63") (name "unconnected-(IC5A-QG-Pad12)") (class "Default")
      (node (ref "IC5") (pin "12") (pinfunction "QG_12") (pintype "output"))
    )
    (net (code "64") (name "unconnected-(IC5A-QH-Pad13)") (class "Default")
      (node (ref "IC5") (pin "13") (pinfunction "QH_13") (pintype "output"))
    )
    (net (code "65") (name "unconnected-(IC6A-QA-Pad3)") (class "Default")
      (node (ref "IC6") (pin "3") (pinfunction "QA_3") (pintype "output"))
    )
    (net (code "66") (name "unconnected-(IC6A-QB-Pad4)") (class "Default")
      (node (ref "IC6") (pin "4") (pinfunction "QB_4") (pintype "output"))
    )
    (net (code "67") (name "unconnected-(IC6A-QD-Pad6)") (class "Default")
      (node (ref "IC6") (pin "6") (pinfunction "QD_6") (pintype "output"))
    )
    (net (code "68") (name "unconnected-(IC6A-QE-Pad10)") (class "Default")
      (node (ref "IC6") (pin "10") (pinfunction "QE_10") (pintype "output"))
    )
    (net (code "69") (name "unconnected-(IC6A-QF-Pad11)") (class "Default")
      (node (ref "IC6") (pin "11") (pinfunction "QF_11") (pintype "output"))
    )
    (net (code "70") (name "unconnected-(IC6A-QG-Pad12)") (class "Default")
      (node (ref "IC6") (pin "12") (pinfunction "QG_12") (pintype "output"))
    )
    (net (code "71") (name "unconnected-(IC6A-QH-Pad13)") (class "Default")
      (node (ref "IC6") (pin "13") (pinfunction "QH_13") (pintype "output"))
    )
    (net (code "72") (name "unconnected-(U$1-PB0-Pad14)") (class "Default")
      (node (ref "U$1") (pin "14") (pinfunction "PB0_14") (pintype "bidirectional"))
    )
    (net (code "73") (name "unconnected-(U$1-PB1-Pad15)") (class "Default")
      (node (ref "U$1") (pin "15") (pinfunction "PB1_15") (pintype "bidirectional"))
    )
    (net (code "74") (name "unconnected-(U$1-PF0-OSC_IN-Pad2)") (class "Default")
      (node (ref "U$1") (pin "2") (pinfunction "PF0-OSC_IN_2") (pintype "bidirectional"))
    )
    (net (code "75") (name "unconnected-(U$1-PF1-OSC_OUT-Pad3)") (class "Default")
      (node (ref "U$1") (pin "3") (pinfunction "PF1-OSC_OUT_3") (pintype "bidirectional"))
    )
    (net (code "76") (name "unconnected-(U$2-NC-Pad6)") (class "Default")
      (node (ref "U$2") (pin "6") (pinfunction "NC_6") (pintype "bidirectional"))
    )
    (net (code "77") (name "unconnected-(U$2-TRIG-Pad2)") (class "Default")
      (node (ref "U$2") (pin "2") (pinfunction "TRIG_2") (pintype "bidirectional"))
    )
    (net (code "78") (name "unconnected-(U$3-NC-Pad6)") (class "Default")
      (node (ref "U$3") (pin "6") (pinfunction "NC_6") (pintype "bidirectional"))
    )
    (net (code "79") (name "unconnected-(U$3-TRIG-Pad2)") (class "Default")
      (node (ref "U$3") (pin "2") (pinfunction "TRIG_2") (pintype "bidirectional"))
    )
    (net (code "80") (name "unconnected-(VR-BP-Pad4)") (class "Default")
      (node (ref "VR") (pin "4") (pinfunction "BP_4") (pintype "input"))
    )
    (net (code "81") (name "unconnected-(X5-Pad4)") (class "Default")
      (node (ref "X5") (pin "4") (pinfunction "4_4") (pintype "input"))
    )
  )
)
